# SCH_esp32_with_RTC_and_SD_card_2024-11-0.net
KiCad netlist of a schematic drawn in EasyEDA
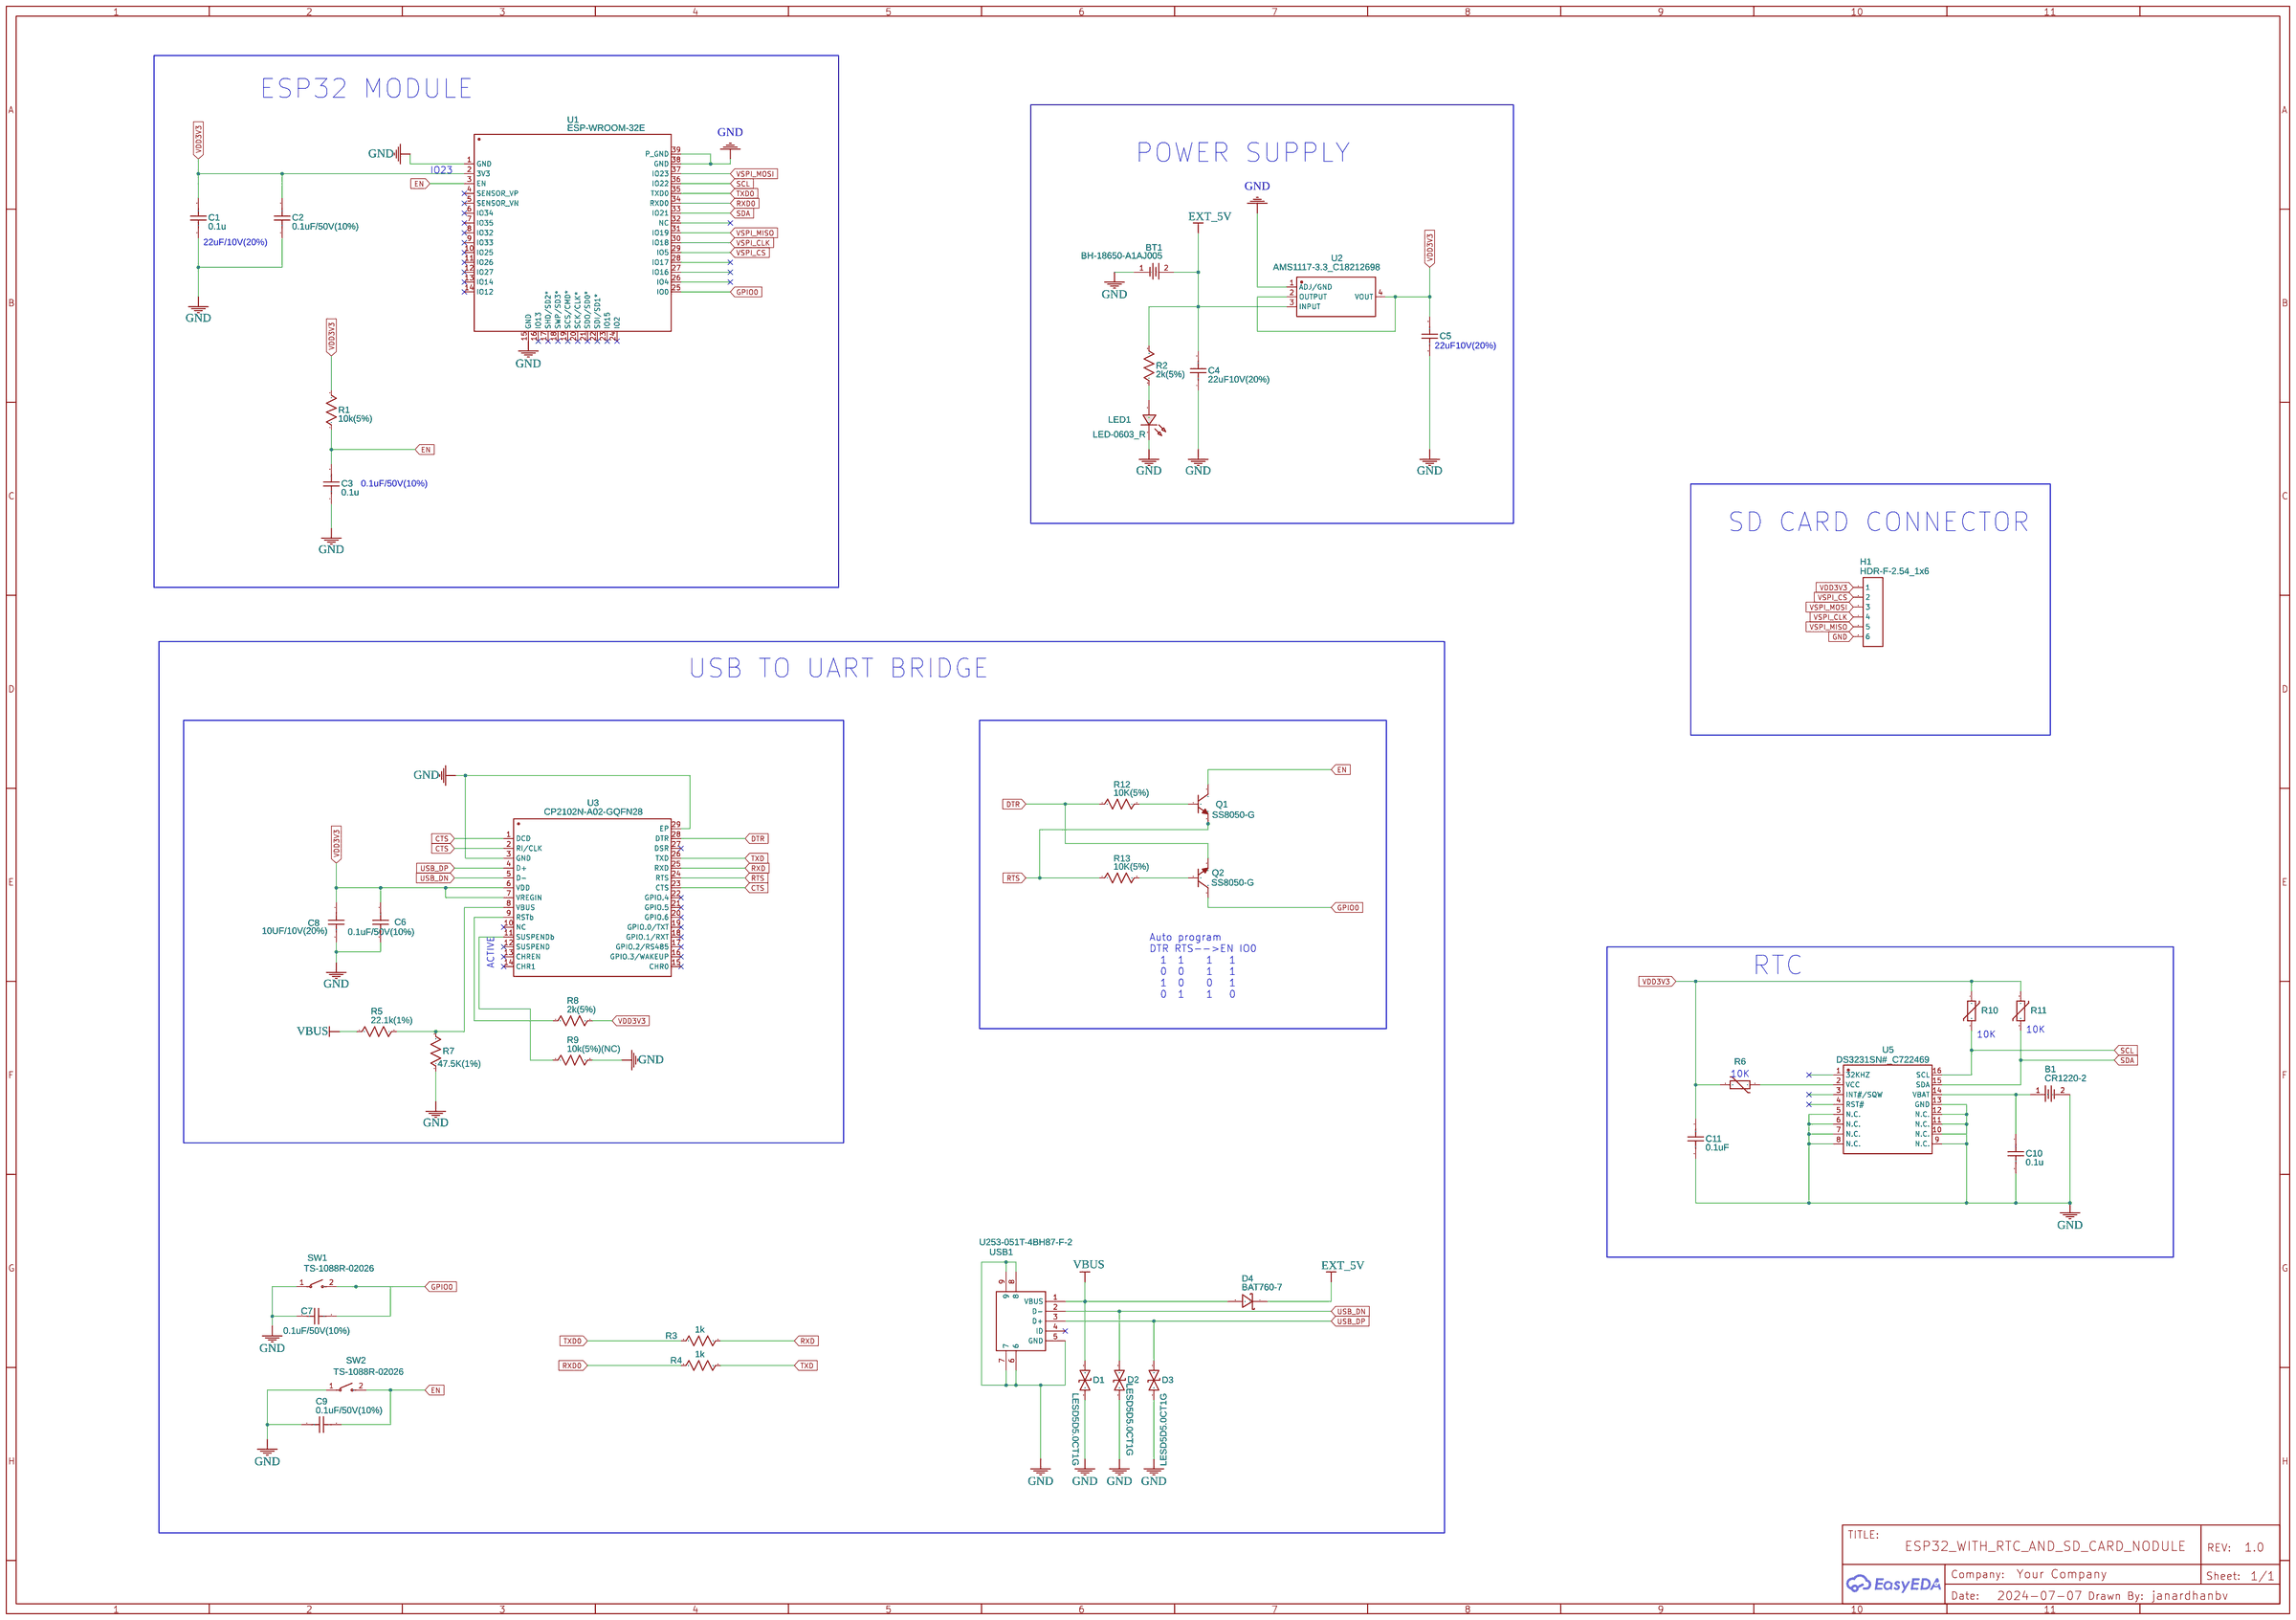
[diagram p0: schematic sheet]

(export (version "E")
  (design (tool "Eeschema 10.0.6"))
  (components
    (comp (ref "B1")
      (value "CR1220-2")
      (fields (field (name "Manufacturer") "Q&J"))
      (libsource (lib "") (part "CR1220-2"))
    )
    (comp (ref "BT1")
      (value "BH-18650-A1AJ005")
      (fields (field (name "Manufacturer") "MYOUNG(美阳)"))
      (libsource (lib "") (part "BH-18650-A1AJ005"))
    )
    (comp (ref "C1") (value "0.1u") (libsource (lib "") (part "C_0603_US")))
    (comp (ref "C2") (value "0.1uF/50V(10%)") (libsource (lib "") (part "C_0603_US")))
    (comp (ref "C3") (value "0.1u") (libsource (lib "") (part "C_0603_US")))
    (comp (ref "C4") (value "22uF10V(20%)") (libsource (lib "") (part "C_0603_US")))
    (comp (ref "C5") (value "0.1u") (libsource (lib "") (part "C_0603_US")))
    (comp (ref "C6") (value "0.1uF/50V(10%)") (libsource (lib "") (part "C_0603_US_1")))
    (comp (ref "C7") (value "0.1uF/50V(10%)") (libsource (lib "") (part "C_0603_US_2")))
    (comp (ref "C8") (value "10UF/10V(20%)") (libsource (lib "") (part "C_0603_US_1")))
    (comp (ref "C9") (value "0.1uF/50V(10%)") (libsource (lib "") (part "C_0603_US_2")))
    (comp (ref "C10") (value "0.1u") (libsource (lib "") (part "C_0603_US_1")))
    (comp (ref "C11") (value "0.1uF") (libsource (lib "") (part "C_0603_US")))
    (comp (ref "D1")
      (value "LESD5D5.0CT1G")
      (fields (field (name "Manufacturer") "LRC(乐山无线电)"))
      (libsource (lib "") (part "LESD5D5.0CT1G"))
    )
    (comp (ref "D2")
      (value "LESD5D5.0CT1G")
      (fields (field (name "Manufacturer") "LRC(乐山无线电)"))
      (libsource (lib "") (part "LESD5D5.0CT1G"))
    )
    (comp (ref "D3")
      (value "LESD5D5.0CT1G")
      (fields (field (name "Manufacturer") "LRC(乐山无线电)"))
      (libsource (lib "") (part "LESD5D5.0CT1G"))
    )
    (comp (ref "D4")
      (value "BAT760-7")
      (fields (field (name "Manufacturer") "DIODES(美台)"))
      (libsource (lib "") (part "BAT760-7"))
    )
    (comp (ref "H1") (value "HDR-F-2.54_1x6") (libsource (lib "") (part "HDR-F-2.54_1x6")))
    (comp (ref "LED1")
      (value "LED-0603_R")
      (fields
        (field (name "Manufacturer Part") "19-217/R6C-AL1M2VY/3T")
        (field (name "Manufacturer") "EVERLIGHT(台湾亿光)")
      )
      (libsource (lib "") (part "LED-0603_R"))
    )
    (comp (ref "Q1")
      (value "SS8050-G")
      (fields (field (name "Manufacturer") "CJ(江苏长电/长晶)"))
      (libsource (lib "") (part "SS8050-G"))
    )
    (comp (ref "Q2")
      (value "SS8050-G")
      (fields (field (name "Manufacturer") "CJ(江苏长电/长晶)"))
      (libsource (lib "") (part "SS8050-G_1"))
    )
    (comp (ref "R1") (value "10k(5%)") (libsource (lib "") (part "R_0603_US")))
    (comp (ref "R2") (value "2k(5%)") (libsource (lib "") (part "R_0603_US")))
    (comp (ref "R3") (value "1k") (libsource (lib "") (part "R_0603_US_1")))
    (comp (ref "R4") (value "1k") (libsource (lib "") (part "R_0603_US_1")))
    (comp (ref "R5") (value "22.1k(1%)") (libsource (lib "") (part "R_0603_US_1")))
    (comp (ref "R6") (value "VARISTOR-5") (libsource (lib "") (part "VARISTOR-5_1")))
    (comp (ref "R7") (value "47.5K(1%)") (libsource (lib "") (part "R_0603_US")))
    (comp (ref "R8") (value "2k(5%)") (libsource (lib "") (part "R_0603_US_1")))
    (comp (ref "R9") (value "10k(5%)(NC)") (libsource (lib "") (part "R_0603_US_1")))
    (comp (ref "R10") (value "VARISTOR-5") (libsource (lib "") (part "VARISTOR-5")))
    (comp (ref "R11") (value "VARISTOR-5") (libsource (lib "") (part "VARISTOR-5")))
    (comp (ref "R12") (value "10K(5%)") (libsource (lib "") (part "R_0603_US_1")))
    (comp (ref "R13") (value "10K(5%)") (libsource (lib "") (part "R_0603_US_1")))
    (comp (ref "SW1")
      (value "TS-1088R-02026")
      (fields (field (name "Manufacturer") "XUNPU(讯普)"))
      (libsource (lib "") (part "TS-1088R-02026"))
    )
    (comp (ref "SW2")
      (value "TS-1088R-02026")
      (fields (field (name "Manufacturer") "XUNPU(讯普)"))
      (libsource (lib "") (part "TS-1088R-02026"))
    )
    (comp (ref "U1")
      (value "ESP-WROOM-32E")
      (fields (field (name "Manufacturer") "DOIT(四博智联)"))
      (libsource (lib "") (part "ESP-WROOM-32E"))
    )
    (comp (ref "U2")
      (value "AMS1117-3.3_C18212698")
      (fields
        (field (name "Manufacturer Part") "AMS1117-3.3")
        (field (name "Manufacturer") "TECH PUBLIC(台舟)")
      )
      (libsource (lib "") (part "AMS1117-3.3_C18212698"))
    )
    (comp (ref "U3")
      (value "CP2102N-A02-GQFN28")
      (fields (field (name "Manufacturer") "SKYWORKS/SILICON LABS(芯科)"))
      (libsource (lib "") (part "CP2102N-A02-GQFN28"))
    )
    (comp (ref "U5")
      (value "DS3231SN#_C722469")
      (fields
        (field (name "Manufacturer Part") "DS3231SN#")
        (field (name "Manufacturer") "ADI(亚德诺)/MAXIM(美信)")
      )
      (libsource (lib "") (part "DS3231SN#_C722469"))
    )
    (comp (ref "USB1")
      (value "U253-051T-4BH87-F-2")
      (fields
        (field (name "Manufacturer Part") "U253-051T-4BH87-S2")
        (field (name "Manufacturer") "XKB Connectivity(中国星坤)")
      )
      (libsource (lib "") (part "U253-051T-4BH87-F-2"))
    )
  )
  (nets
    (net (code "1") (name "CTS") (class "Default")
      (node (ref "U3") (pin "1") (pinfunction "DCD_1") (pintype "unspecified"))
      (node (ref "U3") (pin "2") (pinfunction "RI/CLK_2") (pintype "unspecified"))
      (node (ref "U3") (pin "23") (pinfunction "CTS_23") (pintype "unspecified"))
    )
    (net (code "2") (name "DTR") (class "Default")
      (node (ref "Q2") (pin "2") (pinfunction "E_2") (pintype "input"))
      (node (ref "R12") (pin "1") (pinfunction "1_1") (pintype "unspecified"))
      (node (ref "U3") (pin "28") (pinfunction "DTR_28") (pintype "unspecified"))
    )
    (net (code "3") (name "EN") (class "Default")
      (node (ref "C3") (pin "2") (pinfunction "2_2") (pintype "unspecified"))
      (node (ref "C9") (pin "2") (pinfunction "2_2") (pintype "unspecified"))
      (node (ref "Q1") (pin "3") (pinfunction "C_3") (pintype "input"))
      (node (ref "R1") (pin "1") (pinfunction "1_1") (pintype "unspecified"))
      (node (ref "SW2") (pin "2") (pinfunction "2_2") (pintype "unspecified"))
      (node (ref "U1") (pin "3") (pinfunction "EN_3") (pintype "unspecified"))
    )
    (net (code "4") (name "EXT_5V") (class "Default")
      (node (ref "BT1") (pin "2") (pinfunction "2_2") (pintype "input"))
      (node (ref "C4") (pin "2") (pinfunction "2_2") (pintype "unspecified"))
      (node (ref "D4") (pin "1") (pinfunction "1_1") (pintype "unspecified"))
      (node (ref "R2") (pin "2") (pinfunction "2_2") (pintype "unspecified"))
      (node (ref "U2") (pin "3") (pinfunction "INPUT_3") (pintype "unspecified"))
    )
    (net (code "5") (name "GND") (class "Default")
      (node (ref "B1") (pin "2") (pinfunction "2_2") (pintype "input"))
      (node (ref "BT1") (pin "1") (pinfunction "1_1") (pintype "input"))
      (node (ref "C1") (pin "1") (pinfunction "1_1") (pintype "unspecified"))
      (node (ref "C10") (pin "2") (pinfunction "2_2") (pintype "unspecified"))
      (node (ref "C11") (pin "1") (pinfunction "1_1") (pintype "unspecified"))
      (node (ref "C2") (pin "1") (pinfunction "1_1") (pintype "unspecified"))
      (node (ref "C3") (pin "1") (pinfunction "1_1") (pintype "unspecified"))
      (node (ref "C4") (pin "1") (pinfunction "1_1") (pintype "unspecified"))
      (node (ref "C5") (pin "1") (pinfunction "1_1") (pintype "unspecified"))
      (node (ref "C6") (pin "2") (pinfunction "2_2") (pintype "unspecified"))
      (node (ref "C7") (pin "1") (pinfunction "1_1") (pintype "unspecified"))
      (node (ref "C8") (pin "2") (pinfunction "2_2") (pintype "unspecified"))
      (node (ref "C9") (pin "1") (pinfunction "1_1") (pintype "unspecified"))
      (node (ref "D1") (pin "1") (pinfunction "1_1") (pintype "unspecified"))
      (node (ref "D2") (pin "1") (pinfunction "1_1") (pintype "unspecified"))
      (node (ref "D3") (pin "1") (pinfunction "1_1") (pintype "unspecified"))
      (node (ref "H1") (pin "6") (pinfunction "6_6") (pintype "input"))
      (node (ref "LED1") (pin "2") (pinfunction "2_2") (pintype "unspecified"))
      (node (ref "R7") (pin "1") (pinfunction "1_1") (pintype "unspecified"))
      (node (ref "R9") (pin "2") (pinfunction "2_2") (pintype "unspecified"))
      (node (ref "SW1") (pin "1") (pinfunction "1_1") (pintype "unspecified"))
      (node (ref "SW2") (pin "1") (pinfunction "1_1") (pintype "unspecified"))
      (node (ref "U1") (pin "1") (pinfunction "GND_1") (pintype "unspecified"))
      (node (ref "U1") (pin "15") (pinfunction "GND_15") (pintype "unspecified"))
      (node (ref "U1") (pin "38") (pinfunction "GND_38") (pintype "unspecified"))
      (node (ref "U1") (pin "39") (pinfunction "P_GND_39") (pintype "unspecified"))
      (node (ref "U2") (pin "1") (pinfunction "ADJ/GND_1") (pintype "unspecified"))
      (node (ref "U3") (pin "29") (pinfunction "EP_29") (pintype "unspecified"))
      (node (ref "U3") (pin "3") (pinfunction "GND_3") (pintype "unspecified"))
      (node (ref "U5") (pin "10") (pinfunction "N.C._10") (pintype "unspecified"))
      (node (ref "U5") (pin "11") (pinfunction "N.C._11") (pintype "unspecified"))
      (node (ref "U5") (pin "12") (pinfunction "N.C._12") (pintype "unspecified"))
      (node (ref "U5") (pin "13") (pinfunction "GND_13") (pintype "unspecified"))
      (node (ref "U5") (pin "5") (pinfunction "N.C._5") (pintype "unspecified"))
      (node (ref "U5") (pin "6") (pinfunction "N.C._6") (pintype "unspecified"))
      (node (ref "U5") (pin "7") (pinfunction "N.C._7") (pintype "unspecified"))
      (node (ref "U5") (pin "8") (pinfunction "N.C._8") (pintype "unspecified"))
      (node (ref "U5") (pin "9") (pinfunction "N.C._9") (pintype "unspecified"))
      (node (ref "USB1") (pin "5") (pinfunction "GND_5") (pintype "unspecified"))
      (node (ref "USB1") (pin "6") (pinfunction "6_6") (pintype "unspecified"))
      (node (ref "USB1") (pin "7") (pinfunction "7_7") (pintype "unspecified"))
      (node (ref "USB1") (pin "8") (pinfunction "8_8") (pintype "unspecified"))
      (node (ref "USB1") (pin "9") (pinfunction "9_9") (pintype "unspecified"))
    )
    (net (code "6") (name "GPIO0") (class "Default")
      (node (ref "C7") (pin "2") (pinfunction "2_2") (pintype "unspecified"))
      (node (ref "Q2") (pin "3") (pinfunction "C_3") (pintype "input"))
      (node (ref "SW1") (pin "2") (pinfunction "2_2") (pintype "unspecified"))
      (node (ref "U1") (pin "25") (pinfunction "IO0_25") (pintype "unspecified"))
    )
    (net (code "7") (name "Net-(LED1-Pad1)") (class "Default")
      (node (ref "LED1") (pin "1") (pinfunction "1_1") (pintype "unspecified"))
      (node (ref "R2") (pin "1") (pinfunction "1_1") (pintype "unspecified"))
    )
    (net (code "8") (name "Net-(Q1-B)") (class "Default")
      (node (ref "Q1") (pin "1") (pinfunction "B_1") (pintype "input"))
      (node (ref "R12") (pin "2") (pinfunction "2_2") (pintype "unspecified"))
    )
    (net (code "9") (name "Net-(Q2-B)") (class "Default")
      (node (ref "Q2") (pin "1") (pinfunction "B_1") (pintype "input"))
      (node (ref "R13") (pin "2") (pinfunction "2_2") (pintype "unspecified"))
    )
    (net (code "10") (name "Net-(U3-RSTb)") (class "Default")
      (node (ref "R8") (pin "1") (pinfunction "1_1") (pintype "unspecified"))
      (node (ref "U3") (pin "9") (pinfunction "RSTb_9") (pintype "unspecified"))
    )
    (net (code "11") (name "Net-(U3-SUSPENDb)") (class "Default")
      (node (ref "R9") (pin "1") (pinfunction "1_1") (pintype "unspecified"))
      (node (ref "U3") (pin "11") (pinfunction "SUSPENDb_11") (pintype "unspecified"))
    )
    (net (code "12") (name "Net-(U3-VBUS)") (class "Default")
      (node (ref "R5") (pin "2") (pinfunction "2_2") (pintype "unspecified"))
      (node (ref "R7") (pin "2") (pinfunction "2_2") (pintype "unspecified"))
      (node (ref "U3") (pin "8") (pinfunction "VBUS_8") (pintype "unspecified"))
    )
    (net (code "13") (name "Net-(U5-VBAT)") (class "Default")
      (node (ref "B1") (pin "1") (pinfunction "1_1") (pintype "input"))
      (node (ref "C10") (pin "1") (pinfunction "1_1") (pintype "unspecified"))
      (node (ref "U5") (pin "14") (pinfunction "VBAT_14") (pintype "unspecified"))
    )
    (net (code "14") (name "Net-(U5-VCC)") (class "Default")
      (node (ref "R6") (pin "1") (pinfunction "1_1") (pintype "unspecified"))
      (node (ref "U5") (pin "2") (pinfunction "VCC_2") (pintype "unspecified"))
    )
    (net (code "15") (name "RTS") (class "Default")
      (node (ref "Q1") (pin "2") (pinfunction "E_2") (pintype "input"))
      (node (ref "R13") (pin "1") (pinfunction "1_1") (pintype "unspecified"))
      (node (ref "U3") (pin "24") (pinfunction "RTS_24") (pintype "unspecified"))
    )
    (net (code "16") (name "RXD") (class "Default")
      (node (ref "R3") (pin "2") (pinfunction "2_2") (pintype "unspecified"))
      (node (ref "U3") (pin "25") (pinfunction "RXD_25") (pintype "unspecified"))
    )
    (net (code "17") (name "RXD0") (class "Default")
      (node (ref "R4") (pin "1") (pinfunction "1_1") (pintype "unspecified"))
      (node (ref "U1") (pin "34") (pinfunction "RXD0_34") (pintype "unspecified"))
    )
    (net (code "18") (name "SCL") (class "Default")
      (node (ref "R10") (pin "2") (pinfunction "2_2") (pintype "unspecified"))
      (node (ref "U1") (pin "36") (pinfunction "IO22_36") (pintype "unspecified"))
      (node (ref "U5") (pin "16") (pinfunction "SCL_16") (pintype "unspecified"))
    )
    (net (code "19") (name "SDA") (class "Default")
      (node (ref "R11") (pin "2") (pinfunction "2_2") (pintype "unspecified"))
      (node (ref "U1") (pin "33") (pinfunction "IO21_33") (pintype "unspecified"))
      (node (ref "U5") (pin "15") (pinfunction "SDA_15") (pintype "unspecified"))
    )
    (net (code "20") (name "TXD") (class "Default")
      (node (ref "R4") (pin "2") (pinfunction "2_2") (pintype "unspecified"))
      (node (ref "U3") (pin "26") (pinfunction "TXD_26") (pintype "unspecified"))
    )
    (net (code "21") (name "TXD0") (class "Default")
      (node (ref "R3") (pin "1") (pinfunction "1_1") (pintype "unspecified"))
      (node (ref "U1") (pin "35") (pinfunction "TXD0_35") (pintype "unspecified"))
    )
    (net (code "22") (name "USB_DN") (class "Default")
      (node (ref "D2") (pin "2") (pinfunction "2_2") (pintype "unspecified"))
      (node (ref "U3") (pin "5") (pinfunction "D-_5") (pintype "unspecified"))
      (node (ref "USB1") (pin "2") (pinfunction "D-_2") (pintype "unspecified"))
    )
    (net (code "23") (name "USB_DP") (class "Default")
      (node (ref "D3") (pin "2") (pinfunction "2_2") (pintype "unspecified"))
      (node (ref "U3") (pin "4") (pinfunction "D+_4") (pintype "unspecified"))
      (node (ref "USB1") (pin "3") (pinfunction "D+_3") (pintype "unspecified"))
    )
    (net (code "24") (name "VBUS") (class "Default")
      (node (ref "D1") (pin "2") (pinfunction "2_2") (pintype "unspecified"))
      (node (ref "D4") (pin "2") (pinfunction "2_2") (pintype "unspecified"))
      (node (ref "R5") (pin "1") (pinfunction "1_1") (pintype "unspecified"))
      (node (ref "USB1") (pin "1") (pinfunction "VBUS_1") (pintype "unspecified"))
    )
    (net (code "25") (name "VDD3V3") (class "Default")
      (node (ref "C1") (pin "2") (pinfunction "2_2") (pintype "unspecified"))
      (node (ref "C11") (pin "2") (pinfunction "2_2") (pintype "unspecified"))
      (node (ref "C2") (pin "2") (pinfunction "2_2") (pintype "unspecified"))
      (node (ref "C5") (pin "2") (pinfunction "2_2") (pintype "unspecified"))
      (node (ref "C6") (pin "1") (pinfunction "1_1") (pintype "unspecified"))
      (node (ref "C8") (pin "1") (pinfunction "1_1") (pintype "unspecified"))
      (node (ref "H1") (pin "1") (pinfunction "1_1") (pintype "input"))
      (node (ref "R1") (pin "2") (pinfunction "2_2") (pintype "unspecified"))
      (node (ref "R10") (pin "1") (pinfunction "1_1") (pintype "unspecified"))
      (node (ref "R11") (pin "1") (pinfunction "1_1") (pintype "unspecified"))
      (node (ref "R6") (pin "2") (pinfunction "2_2") (pintype "unspecified"))
      (node (ref "R8") (pin "2") (pinfunction "2_2") (pintype "unspecified"))
      (node (ref "U1") (pin "2") (pinfunction "3V3_2") (pintype "unspecified"))
      (node (ref "U2") (pin "2") (pinfunction "OUTPUT_2") (pintype "unspecified"))
      (node (ref "U2") (pin "4") (pinfunction "VOUT_4") (pintype "unspecified"))
      (node (ref "U3") (pin "6") (pinfunction "VDD_6") (pintype "unspecified"))
      (node (ref "U3") (pin "7") (pinfunction "VREGIN_7") (pintype "unspecified"))
    )
    (net (code "26") (name "VSPI_CLK") (class "Default")
      (node (ref "H1") (pin "4") (pinfunction "4_4") (pintype "input"))
      (node (ref "U1") (pin "30") (pinfunction "IO18_30") (pintype "unspecified"))
    )
    (net (code "27") (name "VSPI_CS") (class "Default")
      (node (ref "H1") (pin "2") (pinfunction "2_2") (pintype "input"))
      (node (ref "U1") (pin "29") (pinfunction "IO5_29") (pintype "unspecified"))
    )
    (net (code "28") (name "VSPI_MISO") (class "Default")
      (node (ref "H1") (pin "5") (pinfunction "5_5") (pintype "input"))
      (node (ref "U1") (pin "31") (pinfunction "IO19_31") (pintype "unspecified"))
    )
    (net (code "29") (name "VSPI_MOSI") (class "Default")
      (node (ref "H1") (pin "3") (pinfunction "3_3") (pintype "input"))
      (node (ref "U1") (pin "37") (pinfunction "IO23_37") (pintype "unspecified"))
    )
    (net (code "30") (name "unconnected-(U1-IO2-Pad24)") (class "Default")
      (node (ref "U1") (pin "24") (pinfunction "IO2_24") (pintype "unspecified+no_connect"))
    )
    (net (code "31") (name "unconnected-(U1-IO4-Pad26)") (class "Default")
      (node (ref "U1") (pin "26") (pinfunction "IO4_26") (pintype "unspecified+no_connect"))
    )
    (net (code "32") (name "unconnected-(U1-IO12-Pad14)") (class "Default")
      (node (ref "U1") (pin "14") (pinfunction "IO12_14") (pintype "unspecified+no_connect"))
    )
    (net (code "33") (name "unconnected-(U1-IO13-Pad16)") (class "Default")
      (node (ref "U1") (pin "16") (pinfunction "IO13_16") (pintype "unspecified+no_connect"))
    )
    (net (code "34") (name "unconnected-(U1-IO14-Pad13)") (class "Default")
      (node (ref "U1") (pin "13") (pinfunction "IO14_13") (pintype "unspecified+no_connect"))
    )
    (net (code "35") (name "unconnected-(U1-IO15-Pad23)") (class "Default")
      (node (ref "U1") (pin "23") (pinfunction "IO15_23") (pintype "unspecified+no_connect"))
    )
    (net (code "36") (name "unconnected-(U1-IO16-Pad27)") (class "Default")
      (node (ref "U1") (pin "27") (pinfunction "IO16_27") (pintype "unspecified+no_connect"))
    )
    (net (code "37") (name "unconnected-(U1-IO17-Pad28)") (class "Default")
      (node (ref "U1") (pin "28") (pinfunction "IO17_28") (pintype "unspecified+no_connect"))
    )
    (net (code "38") (name "unconnected-(U1-IO25-Pad10)") (class "Default")
      (node (ref "U1") (pin "10") (pinfunction "IO25_10") (pintype "unspecified+no_connect"))
    )
    (net (code "39") (name "unconnected-(U1-IO26-Pad11)") (class "Default")
      (node (ref "U1") (pin "11") (pinfunction "IO26_11") (pintype "unspecified+no_connect"))
    )
    (net (code "40") (name "unconnected-(U1-IO27-Pad12)") (class "Default")
      (node (ref "U1") (pin "12") (pinfunction "IO27_12") (pintype "unspecified+no_connect"))
    )
    (net (code "41") (name "unconnected-(U1-IO32-Pad8)") (class "Default")
      (node (ref "U1") (pin "8") (pinfunction "IO32_8") (pintype "unspecified+no_connect"))
    )
    (net (code "42") (name "unconnected-(U1-IO33-Pad9)") (class "Default")
      (node (ref "U1") (pin "9") (pinfunction "IO33_9") (pintype "unspecified+no_connect"))
    )
    (net (code "43") (name "unconnected-(U1-IO34-Pad6)") (class "Default")
      (node (ref "U1") (pin "6") (pinfunction "IO34_6") (pintype "unspecified+no_connect"))
    )
    (net (code "44") (name "unconnected-(U1-IO35-Pad7)") (class "Default")
      (node (ref "U1") (pin "7") (pinfunction "IO35_7") (pintype "unspecified+no_connect"))
    )
    (net (code "45") (name "unconnected-(U1-NC-Pad32)") (class "Default")
      (node (ref "U1") (pin "32") (pinfunction "NC_32") (pintype "unspecified+no_connect"))
    )
    (net (code "46") (name "unconnected-(U1-SCK{slash}CLK*-Pad20)") (class "Default")
      (node (ref "U1") (pin "20") (pinfunction "SCK/CLK*_20") (pintype "unspecified+no_connect"))
    )
    (net (code "47") (name "unconnected-(U1-SCS{slash}CMD*-Pad19)") (class "Default")
      (node (ref "U1") (pin "19") (pinfunction "SCS/CMD*_19") (pintype "unspecified+no_connect"))
    )
    (net (code "48") (name "unconnected-(U1-SDI{slash}SD1*-Pad22)") (class "Default")
      (node (ref "U1") (pin "22") (pinfunction "SDI/SD1*_22") (pintype "unspecified+no_connect"))
    )
    (net (code "49") (name "unconnected-(U1-SDO{slash}SD0*-Pad21)") (class "Default")
      (node (ref "U1") (pin "21") (pinfunction "SDO/SD0*_21") (pintype "unspecified+no_connect"))
    )
    (net (code "50") (name "unconnected-(U1-SENSOR_VN-Pad5)") (class "Default")
      (node (ref "U1") (pin "5") (pinfunction "SENSOR_VN_5") (pintype "unspecified+no_connect"))
    )
    (net (code "51") (name "unconnected-(U1-SENSOR_VP-Pad4)") (class "Default")
      (node (ref "U1") (pin "4") (pinfunction "SENSOR_VP_4") (pintype "unspecified+no_connect"))
    )
    (net (code "52") (name "unconnected-(U1-SHD{slash}SD2*-Pad17)") (class "Default")
      (node (ref "U1") (pin "17") (pinfunction "SHD/SD2*_17") (pintype "unspecified+no_connect"))
    )
    (net (code "53") (name "unconnected-(U1-SWP{slash}SD3*-Pad18)") (class "Default")
      (node (ref "U1") (pin "18") (pinfunction "SWP/SD3*_18") (pintype "unspecified+no_connect"))
    )
    (net (code "54") (name "unconnected-(U3-CHR0-Pad15)") (class "Default")
      (node (ref "U3") (pin "15") (pinfunction "CHR0_15") (pintype "unspecified+no_connect"))
    )
    (net (code "55") (name "unconnected-(U3-CHR1-Pad14)") (class "Default")
      (node (ref "U3") (pin "14") (pinfunction "CHR1_14") (pintype "unspecified+no_connect"))
    )
    (net (code "56") (name "unconnected-(U3-CHREN-Pad13)") (class "Default")
      (node (ref "U3") (pin "13") (pinfunction "CHREN_13") (pintype "unspecified+no_connect"))
    )
    (net (code "57") (name "unconnected-(U3-DSR-Pad27)") (class "Default")
      (node (ref "U3") (pin "27") (pinfunction "DSR_27") (pintype "unspecified+no_connect"))
    )
    (net (code "58") (name "unconnected-(U3-GPIO.0{slash}TXT-Pad19)") (class "Default")
      (node (ref "U3") (pin "19") (pinfunction "GPIO.0/TXT_19") (pintype "unspecified+no_connect"))
    )
    (net (code "59") (name "unconnected-(U3-GPIO.1{slash}RXT-Pad18)") (class "Default")
      (node (ref "U3") (pin "18") (pinfunction "GPIO.1/RXT_18") (pintype "unspecified+no_connect"))
    )
    (net (code "60") (name "unconnected-(U3-GPIO.2{slash}RS485-Pad17)") (class "Default")
      (node (ref "U3") (pin "17") (pinfunction "GPIO.2/RS485_17") (pintype "unspecified+no_connect"))
    )
    (net (code "61") (name "unconnected-(U3-GPIO.3{slash}WAKEUP-Pad16)") (class "Default")
      (node (ref "U3") (pin "16") (pinfunction "GPIO.3/WAKEUP_16") (pintype "unspecified+no_connect"))
    )
    (net (code "62") (name "unconnected-(U3-GPIO.4-Pad22)") (class "Default")
      (node (ref "U3") (pin "22") (pinfunction "GPIO.4_22") (pintype "unspecified+no_connect"))
    )
    (net (code "63") (name "unconnected-(U3-GPIO.5-Pad21)") (class "Default")
      (node (ref "U3") (pin "21") (pinfunction "GPIO.5_21") (pintype "unspecified+no_connect"))
    )
    (net (code "64") (name "unconnected-(U3-GPIO.6-Pad20)") (class "Default")
      (node (ref "U3") (pin "20") (pinfunction "GPIO.6_20") (pintype "unspecified+no_connect"))
    )
    (net (code "65") (name "unconnected-(U3-NC-Pad10)") (class "Default")
      (node (ref "U3") (pin "10") (pinfunction "NC_10") (pintype "unspecified+no_connect"))
    )
    (net (code "66") (name "unconnected-(U3-SUSPEND-Pad12)") (class "Default")
      (node (ref "U3") (pin "12") (pinfunction "SUSPEND_12") (pintype "unspecified+no_connect"))
    )
    (net (code "67") (name "unconnected-(U5-32KHZ-Pad1)") (class "Default")
      (node (ref "U5") (pin "1") (pinfunction "32KHZ_1") (pintype "unspecified+no_connect"))
    )
    (net (code "68") (name "unconnected-(U5-INT#{slash}SQW-Pad3)") (class "Default")
      (node (ref "U5") (pin "3") (pinfunction "INT#/SQW_3") (pintype "unspecified+no_connect"))
    )
    (net (code "69") (name "unconnected-(U5-RST#-Pad4)") (class "Default")
      (node (ref "U5") (pin "4") (pinfunction "RST#_4") (pintype "unspecified+no_connect"))
    )
    (net (code "70") (name "unconnected-(USB1-ID-Pad4)") (class "Default")
      (node (ref "USB1") (pin "4") (pinfunction "ID_4") (pintype "unspecified+no_connect"))
    )
  )
)
